# handheld_temp_sensor_v2.net
KiCad netlist of a schematic drawn in EAGLE
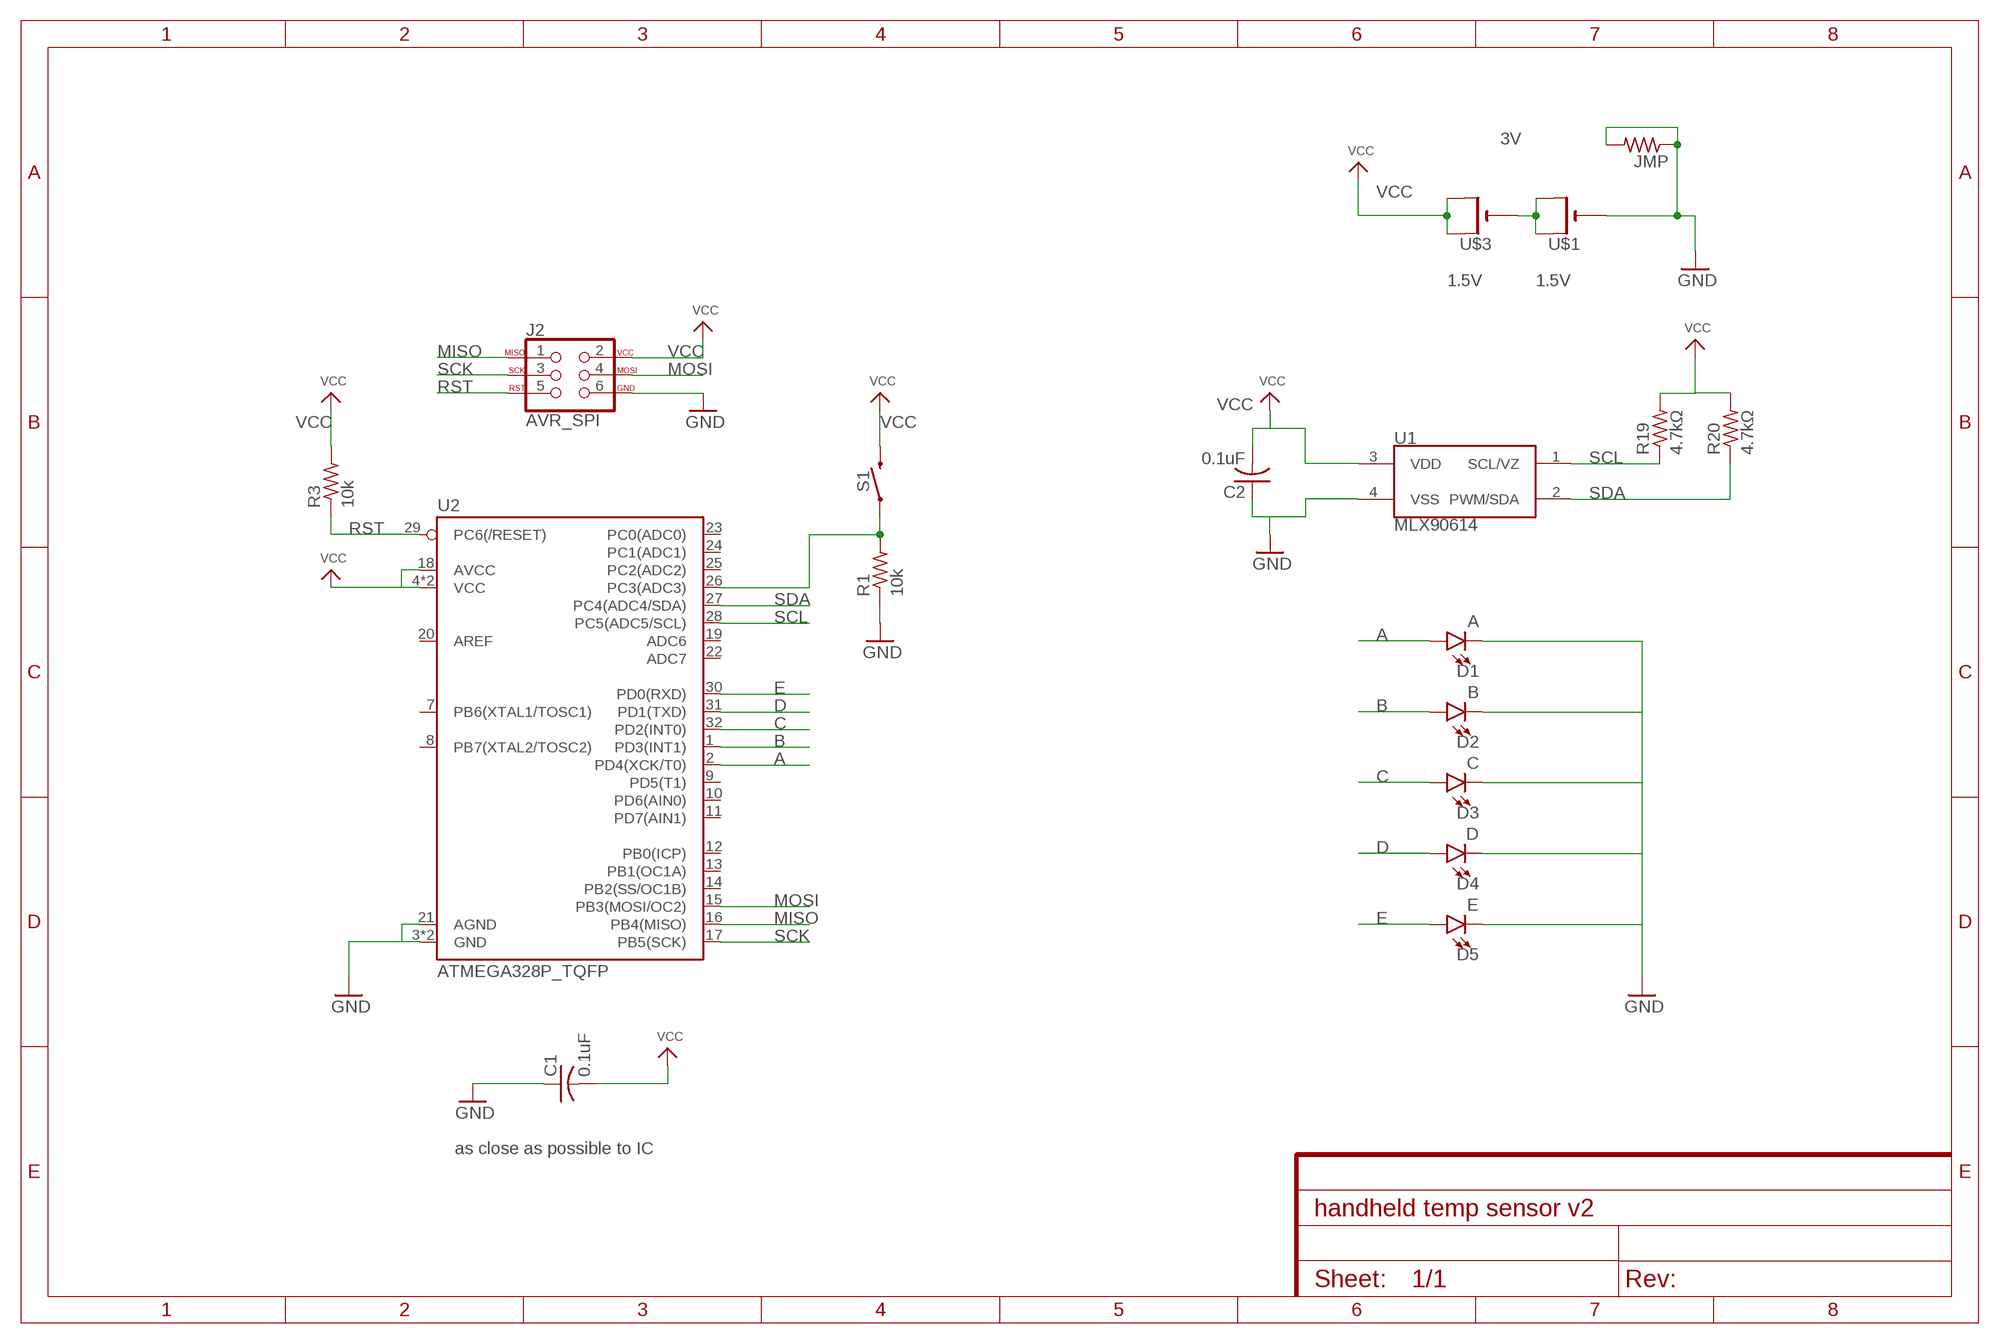
[diagram p0: schematic, sheet 1]

(export (version "E")
  (design (tool "Eeschema 10.0.6"))
  (components
    (comp (ref "C1")
      (value "0.1uF")
      (footprint "eagle-import:C1206")
      (libsource (lib "eagle-import") (part "C-USC1206"))
    )
    (comp (ref "C2")
      (value "0.1uF")
      (footprint "eagle-import:C1206")
      (libsource (lib "eagle-import") (part "C-USC1206"))
    )
    (comp (ref "D1")
      (value "A")
      (footprint "eagle-import:LED-1206")
      (libsource (lib "eagle-import") (part "LED-RED1206"))
    )
    (comp (ref "D2")
      (value "B")
      (footprint "eagle-import:LED-1206")
      (libsource (lib "eagle-import") (part "LED-RED1206"))
    )
    (comp (ref "D3")
      (value "C")
      (footprint "eagle-import:LED-1206")
      (libsource (lib "eagle-import") (part "LED-RED1206"))
    )
    (comp (ref "D4")
      (value "D")
      (footprint "eagle-import:LED-1206")
      (libsource (lib "eagle-import") (part "LED-RED1206"))
    )
    (comp (ref "D5")
      (value "E")
      (footprint "eagle-import:LED-1206")
      (libsource (lib "eagle-import") (part "LED-RED1206"))
    )
    (comp (ref "J2")
      (value "AVR_SPI")
      (footprint "eagle-import:2X3_SMT_POSTS")
      (libsource (lib "eagle-import") (part "AVR_SPI_PROG_3X2SMD"))
    )
    (comp (ref "JMP")
      (value "R-US_R1206")
      (footprint "eagle-import:R1206")
      (libsource (lib "eagle-import") (part "R-US_R1206"))
    )
    (comp (ref "R1")
      (value "10k")
      (footprint "eagle-import:R1206")
      (libsource (lib "eagle-import") (part "R-US_R1206"))
    )
    (comp (ref "R3")
      (value "10k")
      (footprint "eagle-import:R1206")
      (libsource (lib "eagle-import") (part "R-US_R1206"))
    )
    (comp (ref "R19")
      (value "4.7kΩ")
      (footprint "eagle-import:R1206")
      (libsource (lib "eagle-import") (part "R-US_R1206"))
    )
    (comp (ref "R20")
      (value "4.7kΩ")
      (footprint "eagle-import:R1206")
      (libsource (lib "eagle-import") (part "R-US_R1206"))
    )
    (comp (ref "S1")
      (value "MOMENTARY-SWITCH-SPST-PTH-6.0MM")
      (footprint "eagle-import:TACTILE_SWITCH_PTH_6.0MM")
      (libsource (lib "eagle-import") (part "MOMENTARY-SWITCH-SPST-PTH-6.0MM"))
    )
    (comp (ref "U$1")
      (value "CR1220THM")
      (footprint "eagle-import:CR1220-THM")
      (libsource (lib "eagle-import") (part "CR1220THM"))
    )
    (comp (ref "U$3")
      (value "CR1220THM")
      (footprint "eagle-import:CR1220-THM")
      (libsource (lib "eagle-import") (part "CR1220THM"))
    )
    (comp (ref "U1")
      (value "MLX90614")
      (footprint "eagle-import:TO-39")
      (libsource (lib "eagle-import") (part "MLX90614"))
    )
    (comp (ref "U2")
      (value "ATMEGA328P_TQFP")
      (footprint "eagle-import:TQFP32-08")
      (libsource (lib "eagle-import") (part "ATMEGA328P_TQFP"))
    )
  )
  (nets
    (net (code "1") (name "/A") (class "Default")
      (node (ref "D1") (pin "A") (pinfunction "A_A") (pintype "passive"))
      (node (ref "U2") (pin "2") (pinfunction "PD4(XCK/T0)_2") (pintype "bidirectional"))
    )
    (net (code "2") (name "/B") (class "Default")
      (node (ref "D2") (pin "A") (pinfunction "A_A") (pintype "passive"))
      (node (ref "U2") (pin "1") (pinfunction "PD3(INT1)_1") (pintype "bidirectional"))
    )
    (net (code "3") (name "/C") (class "Default")
      (node (ref "D3") (pin "A") (pinfunction "A_A") (pintype "passive"))
      (node (ref "U2") (pin "32") (pinfunction "PD2(INT0)_32") (pintype "bidirectional"))
    )
    (net (code "4") (name "/D") (class "Default")
      (node (ref "D4") (pin "A") (pinfunction "A_A") (pintype "passive"))
      (node (ref "U2") (pin "31") (pinfunction "PD1(TXD)_31") (pintype "bidirectional"))
    )
    (net (code "5") (name "/E") (class "Default")
      (node (ref "D5") (pin "A") (pinfunction "A_A") (pintype "passive"))
      (node (ref "U2") (pin "30") (pinfunction "PD0(RXD)_30") (pintype "bidirectional"))
    )
    (net (code "6") (name "/MISO") (class "Default")
      (node (ref "J2") (pin "1") (pinfunction "1_1") (pintype "passive"))
      (node (ref "U2") (pin "16") (pinfunction "PB4(MISO)_16") (pintype "bidirectional"))
    )
    (net (code "7") (name "/MOSI") (class "Default")
      (node (ref "J2") (pin "4") (pinfunction "4_4") (pintype "passive"))
      (node (ref "U2") (pin "15") (pinfunction "PB3(MOSI/OC2)_15") (pintype "bidirectional"))
    )
    (net (code "8") (name "/RST") (class "Default")
      (node (ref "J2") (pin "5") (pinfunction "5_5") (pintype "passive"))
      (node (ref "R3") (pin "1") (pinfunction "1_1") (pintype "passive"))
      (node (ref "U2") (pin "29") (pinfunction "PC6(/RESET)_29") (pintype "bidirectional"))
    )
    (net (code "9") (name "/SCK") (class "Default")
      (node (ref "J2") (pin "3") (pinfunction "3_3") (pintype "passive"))
      (node (ref "U2") (pin "17") (pinfunction "PB5(SCK)_17") (pintype "bidirectional"))
    )
    (net (code "10") (name "/SCL") (class "Default")
      (node (ref "R19") (pin "1") (pinfunction "1_1") (pintype "passive"))
      (node (ref "U1") (pin "1") (pinfunction "SCL/VZ_1") (pintype "bidirectional"))
      (node (ref "U2") (pin "28") (pinfunction "PC5(ADC5/SCL)_28") (pintype "bidirectional"))
    )
    (net (code "11") (name "/SDA") (class "Default")
      (node (ref "R20") (pin "1") (pinfunction "1_1") (pintype "passive"))
      (node (ref "U1") (pin "2") (pinfunction "PWM/SDA_2") (pintype "bidirectional"))
      (node (ref "U2") (pin "27") (pinfunction "PC4(ADC4/SDA)_27") (pintype "bidirectional"))
    )
    (net (code "12") (name "GND") (class "Default")
      (node (ref "C1") (pin "1") (pinfunction "1_1") (pintype "passive"))
      (node (ref "C2") (pin "1") (pinfunction "1_1") (pintype "passive"))
      (node (ref "D1") (pin "C") (pinfunction "C_C") (pintype "passive"))
      (node (ref "D2") (pin "C") (pinfunction "C_C") (pintype "passive"))
      (node (ref "D3") (pin "C") (pinfunction "C_C") (pintype "passive"))
      (node (ref "D4") (pin "C") (pinfunction "C_C") (pintype "passive"))
      (node (ref "D5") (pin "C") (pinfunction "C_C") (pintype "passive"))
      (node (ref "J2") (pin "6") (pinfunction "6_6") (pintype "passive"))
      (node (ref "JMP") (pin "1") (pinfunction "1_1") (pintype "passive"))
      (node (ref "JMP") (pin "2") (pinfunction "2_2") (pintype "passive"))
      (node (ref "R1") (pin "1") (pinfunction "1_1") (pintype "passive"))
      (node (ref "U$1") (pin "-") (pinfunction "-_-") (pintype "passive"))
      (node (ref "U1") (pin "4") (pinfunction "VSS_4") (pintype "bidirectional"))
      (node (ref "U2") (pin "21") (pinfunction "AGND_21") (pintype "bidirectional"))
      (node (ref "U2") (pin "3") (pinfunction "GND_3") (pintype "bidirectional"))
      (node (ref "U2") (pin "5") (pinfunction "GND_5") (pintype "bidirectional"))
    )
    (net (code "13") (name "Net-(U$1-+)") (class "Default")
      (node (ref "U$1") (pin "+1") (pinfunction "+_+1") (pintype "passive"))
      (node (ref "U$1") (pin "+2") (pinfunction "+1_+2") (pintype "passive"))
      (node (ref "U$3") (pin "-") (pinfunction "-_-") (pintype "passive"))
    )
    (net (code "14") (name "Net-(U2-PC3(ADC3))") (class "Default")
      (node (ref "R1") (pin "2") (pinfunction "2_2") (pintype "passive"))
      (node (ref "S1") (pin "1") (pinfunction "1_1") (pintype "passive"))
      (node (ref "U2") (pin "26") (pinfunction "PC3(ADC3)_26") (pintype "bidirectional"))
    )
    (net (code "15") (name "VCC") (class "Default")
      (node (ref "C1") (pin "2") (pinfunction "2_2") (pintype "passive"))
      (node (ref "C2") (pin "2") (pinfunction "2_2") (pintype "passive"))
      (node (ref "J2") (pin "2") (pinfunction "2_2") (pintype "passive"))
      (node (ref "R19") (pin "2") (pinfunction "2_2") (pintype "passive"))
      (node (ref "R20") (pin "2") (pinfunction "2_2") (pintype "passive"))
      (node (ref "R3") (pin "2") (pinfunction "2_2") (pintype "passive"))
      (node (ref "S1") (pin "3") (pinfunction "2_3") (pintype "passive"))
      (node (ref "U$3") (pin "+1") (pinfunction "+_+1") (pintype "passive"))
      (node (ref "U$3") (pin "+2") (pinfunction "+1_+2") (pintype "passive"))
      (node (ref "U1") (pin "3") (pinfunction "VDD_3") (pintype "bidirectional"))
      (node (ref "U2") (pin "18") (pinfunction "AVCC_18") (pintype "bidirectional"))
      (node (ref "U2") (pin "4") (pinfunction "VCC_4") (pintype "bidirectional"))
      (node (ref "U2") (pin "6") (pinfunction "VCC_6") (pintype "bidirectional"))
    )
    (net (code "16") (name "unconnected-(U2-ADC6-Pad19)") (class "Default")
      (node (ref "U2") (pin "19") (pinfunction "ADC6_19") (pintype "bidirectional"))
    )
    (net (code "17") (name "unconnected-(U2-ADC7-Pad22)") (class "Default")
      (node (ref "U2") (pin "22") (pinfunction "ADC7_22") (pintype "bidirectional"))
    )
    (net (code "18") (name "unconnected-(U2-AREF-Pad20)") (class "Default")
      (node (ref "U2") (pin "20") (pinfunction "AREF_20") (pintype "bidirectional"))
    )
    (net (code "19") (name "unconnected-(U2-PB0(ICP)-Pad12)") (class "Default")
      (node (ref "U2") (pin "12") (pinfunction "PB0(ICP)_12") (pintype "bidirectional"))
    )
    (net (code "20") (name "unconnected-(U2-PB1(OC1A)-Pad13)") (class "Default")
      (node (ref "U2") (pin "13") (pinfunction "PB1(OC1A)_13") (pintype "bidirectional"))
    )
    (net (code "21") (name "unconnected-(U2-PB2(SS{slash}OC1B)-Pad14)") (class "Default")
      (node (ref "U2") (pin "14") (pinfunction "PB2(SS/OC1B)_14") (pintype "bidirectional"))
    )
    (net (code "22") (name "unconnected-(U2-PB6(XTAL1{slash}TOSC1)-Pad7)") (class "Default")
      (node (ref "U2") (pin "7") (pinfunction "PB6(XTAL1/TOSC1)_7") (pintype "bidirectional"))
    )
    (net (code "23") (name "unconnected-(U2-PB7(XTAL2{slash}TOSC2)-Pad8)") (class "Default")
      (node (ref "U2") (pin "8") (pinfunction "PB7(XTAL2/TOSC2)_8") (pintype "bidirectional"))
    )
    (net (code "24") (name "unconnected-(U2-PC0(ADC0)-Pad23)") (class "Default")
      (node (ref "U2") (pin "23") (pinfunction "PC0(ADC0)_23") (pintype "bidirectional"))
    )
    (net (code "25") (name "unconnected-(U2-PC1(ADC1)-Pad24)") (class "Default")
      (node (ref "U2") (pin "24") (pinfunction "PC1(ADC1)_24") (pintype "bidirectional"))
    )
    (net (code "26") (name "unconnected-(U2-PC2(ADC2)-Pad25)") (class "Default")
      (node (ref "U2") (pin "25") (pinfunction "PC2(ADC2)_25") (pintype "bidirectional"))
    )
    (net (code "27") (name "unconnected-(U2-PD5(T1)-Pad9)") (class "Default")
      (node (ref "U2") (pin "9") (pinfunction "PD5(T1)_9") (pintype "bidirectional"))
    )
    (net (code "28") (name "unconnected-(U2-PD6(AIN0)-Pad10)") (class "Default")
      (node (ref "U2") (pin "10") (pinfunction "PD6(AIN0)_10") (pintype "bidirectional"))
    )
    (net (code "29") (name "unconnected-(U2-PD7(AIN1)-Pad11)") (class "Default")
      (node (ref "U2") (pin "11") (pinfunction "PD7(AIN1)_11") (pintype "bidirectional"))
    )
  )
)
